# i2c2midi_board.net
KiCad netlist of a schematic drawn in EAGLE
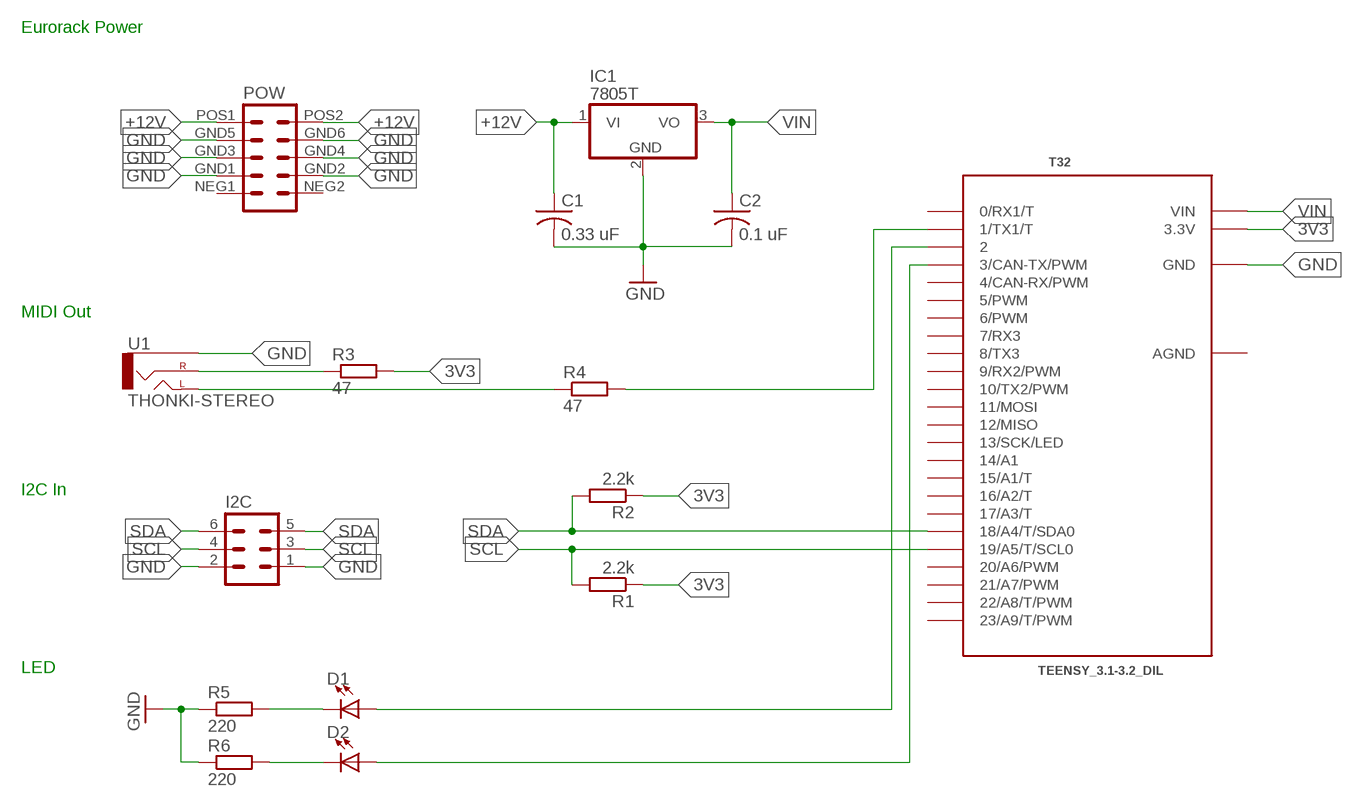
[diagram p0: schematic, sheet 1]

(export (version "E")
  (design (tool "Eeschema 10.0.6"))
  (components
    (comp (ref "C1")
      (value "0.33 uF")
      (footprint "eagle-import:C050-025X075")
      (libsource (lib "eagle-import") (part "C-US050-025X075"))
    )
    (comp (ref "C2")
      (value "0.1 uF")
      (footprint "eagle-import:C050-025X075")
      (libsource (lib "eagle-import") (part "C-US050-025X075"))
    )
    (comp (ref "D1")
      (value "LED3MM")
      (footprint "eagle-import:LED3MM")
      (libsource (lib "eagle-import") (part "LED3MM"))
    )
    (comp (ref "D2")
      (value "LED3MM")
      (footprint "eagle-import:LED3MM")
      (libsource (lib "eagle-import") (part "LED3MM"))
    )
    (comp (ref "I2C")
      (value "MA03-2BACKSIDEFRONTSIDE")
      (footprint "eagle-import:MA03-2")
      (libsource (lib "eagle-import") (part "MA03-2BACKSIDEFRONTSIDE"))
    )
    (comp (ref "IC1")
      (value "7805T")
      (footprint "eagle-import:TO220H")
      (libsource (lib "eagle-import") (part "78T05"))
    )
    (comp (ref "POW")
      (value "EURO_POWER_HEADERLOCK_PADS")
      (footprint "eagle-import:EURO_PWR_HEADER_LOCK")
      (libsource (lib "eagle-import") (part "EURO_POWER_HEADERLOCK_PADS"))
    )
    (comp (ref "R1")
      (value "2.2k")
      (footprint "eagle-import:10MM_RESISTOR")
      (libsource (lib "eagle-import") (part "RESISTOR10MM_RESISTOR"))
    )
    (comp (ref "R2")
      (value "2.2k")
      (footprint "eagle-import:10MM_RESISTOR")
      (libsource (lib "eagle-import") (part "RESISTOR10MM_RESISTOR"))
    )
    (comp (ref "R3")
      (value "47")
      (footprint "eagle-import:10MM_RESISTOR")
      (libsource (lib "eagle-import") (part "RESISTOR10MM_RESISTOR"))
    )
    (comp (ref "R4")
      (value "47")
      (footprint "eagle-import:10MM_RESISTOR")
      (libsource (lib "eagle-import") (part "RESISTOR10MM_RESISTOR"))
    )
    (comp (ref "R5")
      (value "220")
      (footprint "eagle-import:10MM_RESISTOR")
      (libsource (lib "eagle-import") (part "RESISTOR10MM_RESISTOR"))
    )
    (comp (ref "R6")
      (value "220")
      (footprint "eagle-import:10MM_RESISTOR")
      (libsource (lib "eagle-import") (part "RESISTOR10MM_RESISTOR"))
    )
    (comp (ref "T32")
      (value "TEENSY_3.1-3.2_DIL")
      (footprint "eagle-import:TEENSY_3.0-3.2&LC_DIL")
      (libsource (lib "eagle-import") (part "TEENSY_3.1-3.2_DIL"))
    )
    (comp (ref "U1")
      (value "THONKI-STEREO")
      (footprint "eagle-import:WQP-PJ366ST_JACK")
      (libsource (lib "eagle-import") (part "THONKI-STEREO"))
    )
  )
  (nets
    (net (code "1") (name "+12V") (class "Default")
      (node (ref "C1") (pin "1") (pinfunction "1_1") (pintype "passive"))
      (node (ref "IC1") (pin "1") (pinfunction "VI_1") (pintype "input"))
      (node (ref "POW") (pin "POS1") (pinfunction "10_POS1") (pintype "passive"))
      (node (ref "POW") (pin "POS2") (pinfunction "9_POS2") (pintype "passive"))
    )
    (net (code "2") (name "/AGND") (class "Default")
      (node (ref "T32") (pin "AGND") (pinfunction "AGND_AGND") (pintype "power_in"))
    )
    (net (code "3") (name "3V3") (class "Default")
      (node (ref "R1") (pin "1") (pinfunction "1_1") (pintype "passive"))
      (node (ref "R2") (pin "1") (pinfunction "1_1") (pintype "passive"))
      (node (ref "R3") (pin "2") (pinfunction "2_2") (pintype "passive"))
      (node (ref "T32") (pin "3.3V") (pinfunction "3.3V_3.3V") (pintype "power_in"))
    )
    (net (code "4") (name "GND") (class "Default")
      (node (ref "C1") (pin "2") (pinfunction "2_2") (pintype "passive"))
      (node (ref "C2") (pin "2") (pinfunction "2_2") (pintype "passive"))
      (node (ref "I2C") (pin "1") (pinfunction "1_1") (pintype "passive"))
      (node (ref "I2C") (pin "2") (pinfunction "2_2") (pintype "passive"))
      (node (ref "IC1") (pin "2") (pinfunction "GND_2") (pintype "passive"))
      (node (ref "POW") (pin "GND1") (pinfunction "4_GND1") (pintype "passive"))
      (node (ref "POW") (pin "GND2") (pinfunction "3_GND2") (pintype "passive"))
      (node (ref "POW") (pin "GND3") (pinfunction "6_GND3") (pintype "passive"))
      (node (ref "POW") (pin "GND4") (pinfunction "5_GND4") (pintype "passive"))
      (node (ref "POW") (pin "GND5") (pinfunction "8_GND5") (pintype "passive"))
      (node (ref "POW") (pin "GND6") (pinfunction "7_GND6") (pintype "passive"))
      (node (ref "R5") (pin "1") (pinfunction "1_1") (pintype "passive"))
      (node (ref "R6") (pin "1") (pinfunction "1_1") (pintype "passive"))
      (node (ref "T32") (pin "GND") (pinfunction "GND_GND") (pintype "power_in"))
      (node (ref "U1") (pin "P$3_SLEEVE") (pinfunction "SLEEVE_P$3_SLEEVE") (pintype "bidirectional"))
    )
    (net (code "5") (name "Net-(D1-C)") (class "Default")
      (node (ref "D1") (pin "K") (pinfunction "C_K") (pintype "passive"))
      (node (ref "R5") (pin "2") (pinfunction "2_2") (pintype "passive"))
    )
    (net (code "6") (name "Net-(D1-PadA)") (class "Default")
      (node (ref "D1") (pin "A") (pinfunction "A_A") (pintype "passive"))
      (node (ref "T32") (pin "2") (pinfunction "2_2") (pintype "bidirectional"))
    )
    (net (code "7") (name "Net-(D2-C)") (class "Default")
      (node (ref "D2") (pin "K") (pinfunction "C_K") (pintype "passive"))
      (node (ref "R6") (pin "2") (pinfunction "2_2") (pintype "passive"))
    )
    (net (code "8") (name "Net-(T32-1{slash}TX1{slash}T)") (class "Default")
      (node (ref "R4") (pin "2") (pinfunction "2_2") (pintype "passive"))
      (node (ref "T32") (pin "1") (pinfunction "1/TX1/T_1") (pintype "bidirectional"))
    )
    (net (code "9") (name "Net-(T32-3{slash}CAN-TX{slash}PWM)") (class "Default")
      (node (ref "D2") (pin "A") (pinfunction "A_A") (pintype "passive"))
      (node (ref "T32") (pin "3") (pinfunction "3/CAN-TX/PWM_3") (pintype "bidirectional"))
    )
    (net (code "10") (name "Net-(U1-LEFT)") (class "Default")
      (node (ref "R4") (pin "1") (pinfunction "1_1") (pintype "passive"))
      (node (ref "U1") (pin "P$1_TIP") (pinfunction "LEFT_P$1_TIP") (pintype "bidirectional"))
    )
    (net (code "11") (name "Net-(U1-RIGHT)") (class "Default")
      (node (ref "R3") (pin "1") (pinfunction "1_1") (pintype "passive"))
      (node (ref "U1") (pin "P$2_SWITCH") (pinfunction "RIGHT_P$2_SWITCH") (pintype "bidirectional"))
    )
    (net (code "12") (name "SCL") (class "Default")
      (node (ref "I2C") (pin "3") (pinfunction "3_3") (pintype "passive"))
      (node (ref "I2C") (pin "4") (pinfunction "4_4") (pintype "passive"))
      (node (ref "R1") (pin "2") (pinfunction "2_2") (pintype "passive"))
      (node (ref "T32") (pin "19/A5") (pinfunction "19/A5/T/SCL0_19/A5") (pintype "bidirectional"))
    )
    (net (code "13") (name "SDA") (class "Default")
      (node (ref "I2C") (pin "5") (pinfunction "5_5") (pintype "passive"))
      (node (ref "I2C") (pin "6") (pinfunction "6_6") (pintype "passive"))
      (node (ref "R2") (pin "2") (pinfunction "2_2") (pintype "passive"))
      (node (ref "T32") (pin "18/A4") (pinfunction "18/A4/T/SDA0_18/A4") (pintype "bidirectional"))
    )
    (net (code "14") (name "VIN") (class "Default")
      (node (ref "C2") (pin "1") (pinfunction "1_1") (pintype "passive"))
      (node (ref "IC1") (pin "3") (pinfunction "VO_3") (pintype "passive"))
      (node (ref "T32") (pin "VIN") (pinfunction "VIN_VIN") (pintype "power_in"))
    )
    (net (code "15") (name "unconnected-(POW-1-PadNEG2)") (class "Default")
      (node (ref "POW") (pin "NEG2") (pinfunction "1_NEG2") (pintype "passive"))
    )
    (net (code "16") (name "unconnected-(POW-2-PadNEG1)") (class "Default")
      (node (ref "POW") (pin "NEG1") (pinfunction "2_NEG1") (pintype "passive"))
    )
    (net (code "17") (name "unconnected-(T32-0{slash}RX1{slash}T-Pad0)") (class "Default")
      (node (ref "T32") (pin "0") (pinfunction "0/RX1/T_0") (pintype "bidirectional"))
    )
    (net (code "18") (name "unconnected-(T32-4{slash}CAN-RX{slash}PWM-Pad4)") (class "Default")
      (node (ref "T32") (pin "4") (pinfunction "4/CAN-RX/PWM_4") (pintype "bidirectional"))
    )
    (net (code "19") (name "unconnected-(T32-5{slash}PWM-Pad5)") (class "Default")
      (node (ref "T32") (pin "5") (pinfunction "5/PWM_5") (pintype "bidirectional"))
    )
    (net (code "20") (name "unconnected-(T32-6{slash}PWM-Pad6)") (class "Default")
      (node (ref "T32") (pin "6") (pinfunction "6/PWM_6") (pintype "bidirectional"))
    )
    (net (code "21") (name "unconnected-(T32-7{slash}RX3-Pad7)") (class "Default")
      (node (ref "T32") (pin "7") (pinfunction "7/RX3_7") (pintype "bidirectional"))
    )
    (net (code "22") (name "unconnected-(T32-8{slash}TX3-Pad8)") (class "Default")
      (node (ref "T32") (pin "8") (pinfunction "8/TX3_8") (pintype "bidirectional"))
    )
    (net (code "23") (name "unconnected-(T32-9{slash}RX2{slash}PWM-Pad9)") (class "Default")
      (node (ref "T32") (pin "9") (pinfunction "9/RX2/PWM_9") (pintype "bidirectional"))
    )
    (net (code "24") (name "unconnected-(T32-10{slash}TX2{slash}PWM-Pad10)") (class "Default")
      (node (ref "T32") (pin "10") (pinfunction "10/TX2/PWM_10") (pintype "bidirectional"))
    )
    (net (code "25") (name "unconnected-(T32-11{slash}MOSI-Pad11)") (class "Default")
      (node (ref "T32") (pin "11") (pinfunction "11/MOSI_11") (pintype "bidirectional"))
    )
    (net (code "26") (name "unconnected-(T32-12{slash}MISO-Pad12)") (class "Default")
      (node (ref "T32") (pin "12") (pinfunction "12/MISO_12") (pintype "bidirectional"))
    )
    (net (code "27") (name "unconnected-(T32-13{slash}SCK{slash}LED-Pad13)") (class "Default")
      (node (ref "T32") (pin "13") (pinfunction "13/SCK/LED_13") (pintype "bidirectional"))
    )
    (net (code "28") (name "unconnected-(T32-14{slash}A1-Pad14{slash}A0)") (class "Default")
      (node (ref "T32") (pin "14/A0") (pinfunction "14/A1_14/A0") (pintype "bidirectional"))
    )
    (net (code "29") (name "unconnected-(T32-15{slash}A1{slash}T-Pad15{slash}A1)") (class "Default")
      (node (ref "T32") (pin "15/A1") (pinfunction "15/A1/T_15/A1") (pintype "bidirectional"))
    )
    (net (code "30") (name "unconnected-(T32-16{slash}A2{slash}T-Pad16{slash}A2)") (class "Default")
      (node (ref "T32") (pin "16/A2") (pinfunction "16/A2/T_16/A2") (pintype "bidirectional"))
    )
    (net (code "31") (name "unconnected-(T32-17{slash}A3{slash}T-Pad17{slash}A3)") (class "Default")
      (node (ref "T32") (pin "17/A3") (pinfunction "17/A3/T_17/A3") (pintype "bidirectional"))
    )
    (net (code "32") (name "unconnected-(T32-20{slash}A6{slash}PWM-Pad20{slash}A6)") (class "Default")
      (node (ref "T32") (pin "20/A6") (pinfunction "20/A6/PWM_20/A6") (pintype "bidirectional"))
    )
    (net (code "33") (name "unconnected-(T32-21{slash}A7{slash}PWM-Pad21{slash}A7)") (class "Default")
      (node (ref "T32") (pin "21/A7") (pinfunction "21/A7/PWM_21/A7") (pintype "bidirectional"))
    )
    (net (code "34") (name "unconnected-(T32-22{slash}A8{slash}T{slash}PWM-Pad22{slash}A8)") (class "Default")
      (node (ref "T32") (pin "22/A8") (pinfunction "22/A8/T/PWM_22/A8") (pintype "bidirectional"))
    )
    (net (code "35") (name "unconnected-(T32-23{slash}A9{slash}T{slash}PWM-Pad23{slash}A9)") (class "Default")
      (node (ref "T32") (pin "23/A9") (pinfunction "23/A9/T/PWM_23/A9") (pintype "bidirectional"))
    )
  )
)
